# LED_Fret2.net
KiCad netlist of a schematic drawn in Altium Designer
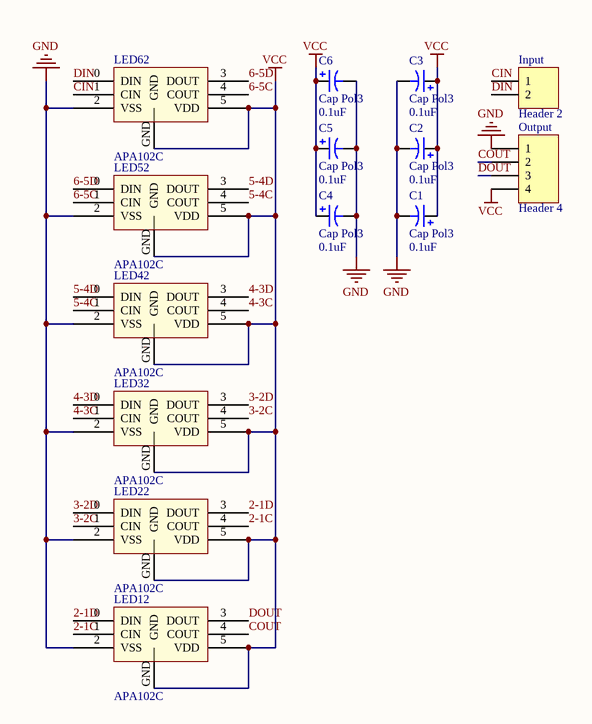
[diagram p0: LED_Fret2.SchDoc]

(export (version "E")
  (design (tool "Eeschema 10.0.6"))
  (components
    (comp (ref "C1")
      (value "Cap Pol3")
      (footprint "C0805")
      (description "Polarized Capacitor (Surface Mount)")
      (fields (field (name "ALTIUM_VALUE") "0.1uF") (field (name "PUBLISHER") "Altium Limited"))
      (libsource (lib "Miscellaneous Devices") (part "Cap Pol3"))
    )
    (comp (ref "C2")
      (value "Cap Pol3")
      (footprint "C0805")
      (description "Polarized Capacitor (Surface Mount)")
      (fields (field (name "ALTIUM_VALUE") "0.1uF") (field (name "PUBLISHER") "Altium Limited"))
      (libsource (lib "Miscellaneous Devices") (part "Cap Pol3"))
    )
    (comp (ref "C3")
      (value "Cap Pol3")
      (footprint "C0805")
      (description "Polarized Capacitor (Surface Mount)")
      (fields (field (name "ALTIUM_VALUE") "0.1uF") (field (name "PUBLISHER") "Altium Limited"))
      (libsource (lib "Miscellaneous Devices") (part "Cap Pol3"))
    )
    (comp (ref "C4")
      (value "Cap Pol3")
      (footprint "C0805")
      (description "Polarized Capacitor (Surface Mount)")
      (fields (field (name "ALTIUM_VALUE") "0.1uF") (field (name "PUBLISHER") "Altium Limited"))
      (libsource (lib "Miscellaneous Devices") (part "Cap Pol3"))
    )
    (comp (ref "C5")
      (value "Cap Pol3")
      (footprint "C0805")
      (description "Polarized Capacitor (Surface Mount)")
      (fields (field (name "ALTIUM_VALUE") "0.1uF") (field (name "PUBLISHER") "Altium Limited"))
      (libsource (lib "Miscellaneous Devices") (part "Cap Pol3"))
    )
    (comp (ref "C6")
      (value "Cap Pol3")
      (footprint "C0805")
      (description "Polarized Capacitor (Surface Mount)")
      (fields (field (name "ALTIUM_VALUE") "0.1uF") (field (name "PUBLISHER") "Altium Limited"))
      (libsource (lib "Miscellaneous Devices") (part "Cap Pol3"))
    )
    (comp (ref "Input")
      (value "Header 2")
      (footprint "HDR1X2")
      (description "Header, 2-Pin")
      (fields (field (name "PUBLISHER") "Altium Limited"))
      (libsource (lib "Miscellaneous Connectors") (part "Header 2"))
    )
    (comp (ref "LED12")
      (value "APA102C")
      (footprint "RGB LED")
      (libsource (lib "Senior_SCH_Lib") (part "RGB LED"))
    )
    (comp (ref "LED22")
      (value "APA102C")
      (footprint "RGB LED")
      (libsource (lib "Senior_SCH_Lib") (part "RGB LED"))
    )
    (comp (ref "LED32")
      (value "APA102C")
      (footprint "RGB LED")
      (libsource (lib "Senior_SCH_Lib") (part "RGB LED"))
    )
    (comp (ref "LED42")
      (value "APA102C")
      (footprint "RGB LED")
      (libsource (lib "Senior_SCH_Lib") (part "RGB LED"))
    )
    (comp (ref "LED52")
      (value "APA102C")
      (footprint "RGB LED")
      (libsource (lib "Senior_SCH_Lib") (part "RGB LED"))
    )
    (comp (ref "LED62")
      (value "APA102C")
      (footprint "RGB LED")
      (libsource (lib "Senior_SCH_Lib") (part "RGB LED"))
    )
    (comp (ref "Output")
      (value "Header 4")
      (footprint "HDR1X4")
      (description "Header, 4-Pin")
      (fields (field (name "PUBLISHER") "Altium Limited"))
      (libsource (lib "Miscellaneous Connectors") (part "Header 4"))
    )
  )
  (nets
    (net (code "1") (name "/2-1C") (class "Default")
      (node (ref "LED12") (pin "1") (pinfunction "CIN_1") (pintype "passive"))
      (node (ref "LED22") (pin "4") (pinfunction "COUT_4") (pintype "passive"))
    )
    (net (code "2") (name "/2-1D") (class "Default")
      (node (ref "LED12") (pin "0") (pinfunction "DIN_0") (pintype "passive"))
      (node (ref "LED22") (pin "3") (pinfunction "DOUT_3") (pintype "passive"))
    )
    (net (code "3") (name "/3-2C") (class "Default")
      (node (ref "LED22") (pin "1") (pinfunction "CIN_1") (pintype "passive"))
      (node (ref "LED32") (pin "4") (pinfunction "COUT_4") (pintype "passive"))
    )
    (net (code "4") (name "/3-2D") (class "Default")
      (node (ref "LED22") (pin "0") (pinfunction "DIN_0") (pintype "passive"))
      (node (ref "LED32") (pin "3") (pinfunction "DOUT_3") (pintype "passive"))
    )
    (net (code "5") (name "/4-3C") (class "Default")
      (node (ref "LED32") (pin "1") (pinfunction "CIN_1") (pintype "passive"))
      (node (ref "LED42") (pin "4") (pinfunction "COUT_4") (pintype "passive"))
    )
    (net (code "6") (name "/4-3D") (class "Default")
      (node (ref "LED32") (pin "0") (pinfunction "DIN_0") (pintype "passive"))
      (node (ref "LED42") (pin "3") (pinfunction "DOUT_3") (pintype "passive"))
    )
    (net (code "7") (name "/5-4C") (class "Default")
      (node (ref "LED42") (pin "1") (pinfunction "CIN_1") (pintype "passive"))
      (node (ref "LED52") (pin "4") (pinfunction "COUT_4") (pintype "passive"))
    )
    (net (code "8") (name "/5-4D") (class "Default")
      (node (ref "LED42") (pin "0") (pinfunction "DIN_0") (pintype "passive"))
      (node (ref "LED52") (pin "3") (pinfunction "DOUT_3") (pintype "passive"))
    )
    (net (code "9") (name "/6-5C") (class "Default")
      (node (ref "LED52") (pin "1") (pinfunction "CIN_1") (pintype "passive"))
      (node (ref "LED62") (pin "4") (pinfunction "COUT_4") (pintype "passive"))
    )
    (net (code "10") (name "/6-5D") (class "Default")
      (node (ref "LED52") (pin "0") (pinfunction "DIN_0") (pintype "passive"))
      (node (ref "LED62") (pin "3") (pinfunction "DOUT_3") (pintype "passive"))
    )
    (net (code "11") (name "/CIN") (class "Default")
      (node (ref "Input") (pin "1") (pinfunction "1_1") (pintype "passive"))
      (node (ref "LED62") (pin "1") (pinfunction "CIN_1") (pintype "passive"))
    )
    (net (code "12") (name "/COUT") (class "Default")
      (node (ref "LED12") (pin "4") (pinfunction "COUT_4") (pintype "passive"))
      (node (ref "Output") (pin "2") (pinfunction "2_2") (pintype "passive"))
    )
    (net (code "13") (name "/DIN") (class "Default")
      (node (ref "Input") (pin "2") (pinfunction "2_2") (pintype "passive"))
      (node (ref "LED62") (pin "0") (pinfunction "DIN_0") (pintype "passive"))
    )
    (net (code "14") (name "/DOUT") (class "Default")
      (node (ref "LED12") (pin "3") (pinfunction "DOUT_3") (pintype "passive"))
      (node (ref "Output") (pin "3") (pinfunction "3_3") (pintype "passive"))
    )
    (net (code "15") (name "GND") (class "Default")
      (node (ref "C1") (pin "2") (pinfunction "2_2") (pintype "passive"))
      (node (ref "C2") (pin "2") (pinfunction "2_2") (pintype "passive"))
      (node (ref "C3") (pin "2") (pinfunction "2_2") (pintype "passive"))
      (node (ref "C4") (pin "2") (pinfunction "2_2") (pintype "passive"))
      (node (ref "C5") (pin "2") (pinfunction "2_2") (pintype "passive"))
      (node (ref "C6") (pin "2") (pinfunction "2_2") (pintype "passive"))
      (node (ref "LED12") (pin "2") (pinfunction "VSS_2") (pintype "passive"))
      (node (ref "LED22") (pin "2") (pinfunction "VSS_2") (pintype "passive"))
      (node (ref "LED32") (pin "2") (pinfunction "VSS_2") (pintype "passive"))
      (node (ref "LED42") (pin "2") (pinfunction "VSS_2") (pintype "passive"))
      (node (ref "LED52") (pin "2") (pinfunction "VSS_2") (pintype "passive"))
      (node (ref "LED62") (pin "2") (pinfunction "VSS_2") (pintype "passive"))
      (node (ref "Output") (pin "1") (pinfunction "1_1") (pintype "passive"))
    )
    (net (code "16") (name "VCC") (class "Default")
      (node (ref "C1") (pin "1") (pinfunction "1_1") (pintype "passive"))
      (node (ref "C2") (pin "1") (pinfunction "1_1") (pintype "passive"))
      (node (ref "C3") (pin "1") (pinfunction "1_1") (pintype "passive"))
      (node (ref "C4") (pin "1") (pinfunction "1_1") (pintype "passive"))
      (node (ref "C5") (pin "1") (pinfunction "1_1") (pintype "passive"))
      (node (ref "C6") (pin "1") (pinfunction "1_1") (pintype "passive"))
      (node (ref "LED12") (pin "5") (pinfunction "VDD_5") (pintype "passive"))
      (node (ref "LED12") (pin "GND") (pinfunction "GND_GND") (pintype "passive"))
      (node (ref "LED22") (pin "5") (pinfunction "VDD_5") (pintype "passive"))
      (node (ref "LED22") (pin "GND") (pinfunction "GND_GND") (pintype "passive"))
      (node (ref "LED32") (pin "5") (pinfunction "VDD_5") (pintype "passive"))
      (node (ref "LED32") (pin "GND") (pinfunction "GND_GND") (pintype "passive"))
      (node (ref "LED42") (pin "5") (pinfunction "VDD_5") (pintype "passive"))
      (node (ref "LED42") (pin "GND") (pinfunction "GND_GND") (pintype "passive"))
      (node (ref "LED52") (pin "5") (pinfunction "VDD_5") (pintype "passive"))
      (node (ref "LED52") (pin "GND") (pinfunction "GND_GND") (pintype "passive"))
      (node (ref "LED62") (pin "5") (pinfunction "VDD_5") (pintype "passive"))
      (node (ref "LED62") (pin "GND") (pinfunction "GND_GND") (pintype "passive"))
      (node (ref "Output") (pin "4") (pinfunction "4_4") (pintype "passive"))
    )
  )
)
